# MAX485.net
KiCad netlist of a schematic drawn in Altium Designer
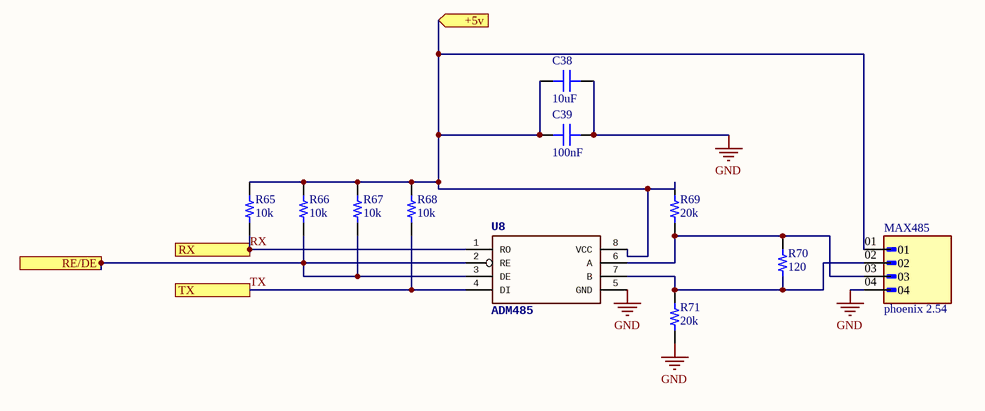
[diagram p0: MAX485.SchDoc]

(export (version "E")
  (design (tool "Eeschema 10.0.6"))
  (components
    (comp (ref "C38")
      (value "10uF")
      (footprint "CAP 0805_2012")
      (description "SMT Capacitor")
      (libsource (lib "Capacitor") (part "Cap 0805"))
    )
    (comp (ref "C39")
      (value "100nF")
      (footprint "CAP 0805_2012")
      (description "SMT Capacitor")
      (libsource (lib "Capacitor") (part "Cap 0805"))
    )
    (comp (ref "MAX485")
      (value "phoenix 2.54")
      (footprint "PHOENIX_1881574")
      (fields (field (name "MF") "{'manufacturer': u'Phoenix Contact'}") (field (name "MP") "1881574"))
      (libsource (lib "1881574") (part "1881574"))
    )
    (comp (ref "R65")
      (value "10k")
      (footprint "RES 0805_2012")
      (description "SMT Resistor")
      (libsource (lib "Resistor") (part "Res 0805"))
    )
    (comp (ref "R66")
      (value "10k")
      (footprint "RES 0805_2012")
      (description "SMT Resistor")
      (libsource (lib "Resistor") (part "Res 0805"))
    )
    (comp (ref "R67")
      (value "10k")
      (footprint "RES 0805_2012")
      (description "SMT Resistor")
      (libsource (lib "Resistor") (part "Res 0805"))
    )
    (comp (ref "R68")
      (value "10k")
      (footprint "RES 0805_2012")
      (description "SMT Resistor")
      (libsource (lib "Resistor") (part "Res 0805"))
    )
    (comp (ref "R69")
      (value "20k")
      (footprint "RES 0805_2012")
      (description "SMT Resistor")
      (libsource (lib "Resistor") (part "Res 0805"))
    )
    (comp (ref "R70")
      (value "120")
      (footprint "RES 0805_2012")
      (description "SMT Resistor")
      (libsource (lib "Resistor") (part "Res 0805"))
    )
    (comp (ref "R71")
      (value "20k")
      (footprint "RES 0805_2012")
      (description "SMT Resistor")
      (libsource (lib "Resistor") (part "Res 0805"))
    )
    (comp (ref "U8")
      (value "ADM485")
      (footprint "SOIC-8 4.9X3.9MM P1.27MM")
      (description "RS485 Interface")
      (fields (field (name "PARTNUMBER") "ADM4853ARZ-REEL7"))
      (libsource (lib "Chip") (part "ADM485 (SMD)"))
    )
  )
  (nets
    (net (code "1") (name "/+5v") (class "Default")
      (node (ref "C38") (pin "1") (pinfunction "1_1") (pintype "passive"))
      (node (ref "C39") (pin "1") (pinfunction "1_1") (pintype "passive"))
      (node (ref "MAX485") (pin "01") (pinfunction "01_01") (pintype "passive"))
      (node (ref "R65") (pin "2") (pinfunction "2_2") (pintype "passive"))
      (node (ref "R66") (pin "2") (pinfunction "2_2") (pintype "passive"))
      (node (ref "R67") (pin "2") (pinfunction "2_2") (pintype "passive"))
      (node (ref "R68") (pin "2") (pinfunction "2_2") (pintype "passive"))
      (node (ref "R69") (pin "2") (pinfunction "2_2") (pintype "passive"))
      (node (ref "U8") (pin "8") (pinfunction "VCC_8") (pintype "passive"))
    )
    (net (code "2") (name "/RE{slash}DE") (class "Default")
      (node (ref "R66") (pin "1") (pinfunction "1_1") (pintype "passive"))
      (node (ref "R67") (pin "1") (pinfunction "1_1") (pintype "passive"))
      (node (ref "U8") (pin "2") (pinfunction "RE_2") (pintype "passive"))
      (node (ref "U8") (pin "3") (pinfunction "DE_3") (pintype "passive"))
    )
    (net (code "3") (name "/RX") (class "Default")
      (node (ref "R65") (pin "1") (pinfunction "1_1") (pintype "passive"))
      (node (ref "U8") (pin "1") (pinfunction "RO_1") (pintype "passive"))
    )
    (net (code "4") (name "/TX") (class "Default")
      (node (ref "R68") (pin "1") (pinfunction "1_1") (pintype "passive"))
      (node (ref "U8") (pin "4") (pinfunction "DI_4") (pintype "passive"))
    )
    (net (code "5") (name "GND") (class "Default")
      (node (ref "C38") (pin "2") (pinfunction "2_2") (pintype "passive"))
      (node (ref "C39") (pin "2") (pinfunction "2_2") (pintype "passive"))
      (node (ref "MAX485") (pin "04") (pinfunction "04_04") (pintype "passive"))
      (node (ref "R71") (pin "1") (pinfunction "1_1") (pintype "passive"))
      (node (ref "U8") (pin "5") (pinfunction "GND_5") (pintype "passive"))
    )
    (net (code "6") (name "Net-(U8-A)") (class "Default")
      (node (ref "MAX485") (pin "03") (pinfunction "03_03") (pintype "passive"))
      (node (ref "R69") (pin "1") (pinfunction "1_1") (pintype "passive"))
      (node (ref "R70") (pin "2") (pinfunction "2_2") (pintype "passive"))
      (node (ref "U8") (pin "6") (pinfunction "A_6") (pintype "passive"))
    )
    (net (code "7") (name "Net-(U8-B)") (class "Default")
      (node (ref "MAX485") (pin "02") (pinfunction "02_02") (pintype "passive"))
      (node (ref "R70") (pin "1") (pinfunction "1_1") (pintype "passive"))
      (node (ref "R71") (pin "2") (pinfunction "2_2") (pintype "passive"))
      (node (ref "U8") (pin "7") (pinfunction "B_7") (pintype "passive"))
    )
  )
)
